# Led_Matrix_3.net
KiCad netlist of a schematic drawn in Altium Designer
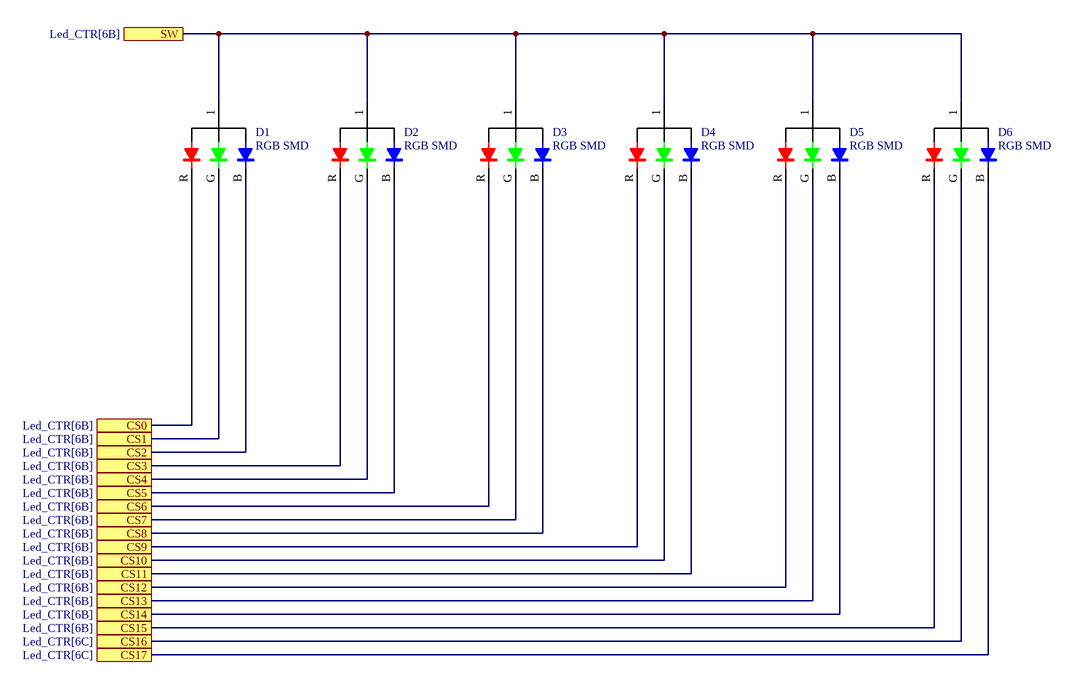
[diagram p0: Led_Matrix_3.SchDoc]

(export (version "E")
  (design (tool "Eeschema 10.0.6"))
  (components
    (comp (ref "D1")
      (value "RGB SMD")
      (footprint "LRTB_R48G")
      (description "LED Tri-Color Blue/Green/Red, 4-Pin Chip, 125 mcd, 2.7V, 10mA")
      (fields
        (field (name "MANUFACTURER") "Osram Opto")
        (field (name "MANUFACTURER PART NUMBER") "LRTB R48G")
      )
      (libsource (lib "Led_Matrix") (part "LED_RGB_SMD-4PIN_LRTB-R48G"))
    )
    (comp (ref "D2")
      (value "RGB SMD")
      (footprint "LRTB_R48G")
      (description "LED Tri-Color Blue/Green/Red, 4-Pin Chip, 125 mcd, 2.7V, 10mA")
      (fields
        (field (name "MANUFACTURER") "Osram Opto")
        (field (name "MANUFACTURER PART NUMBER") "LRTB R48G")
      )
      (libsource (lib "Led_Matrix") (part "LED_RGB_SMD-4PIN_LRTB-R48G"))
    )
    (comp (ref "D3")
      (value "RGB SMD")
      (footprint "LRTB_R48G")
      (description "LED Tri-Color Blue/Green/Red, 4-Pin Chip, 125 mcd, 2.7V, 10mA")
      (fields
        (field (name "MANUFACTURER") "Osram Opto")
        (field (name "MANUFACTURER PART NUMBER") "LRTB R48G")
      )
      (libsource (lib "Led_Matrix") (part "LED_RGB_SMD-4PIN_LRTB-R48G"))
    )
    (comp (ref "D4")
      (value "RGB SMD")
      (footprint "LRTB_R48G")
      (description "LED Tri-Color Blue/Green/Red, 4-Pin Chip, 125 mcd, 2.7V, 10mA")
      (fields
        (field (name "MANUFACTURER") "Osram Opto")
        (field (name "MANUFACTURER PART NUMBER") "LRTB R48G")
      )
      (libsource (lib "Led_Matrix") (part "LED_RGB_SMD-4PIN_LRTB-R48G"))
    )
    (comp (ref "D5")
      (value "RGB SMD")
      (footprint "LRTB_R48G")
      (description "LED Tri-Color Blue/Green/Red, 4-Pin Chip, 125 mcd, 2.7V, 10mA")
      (fields
        (field (name "MANUFACTURER") "Osram Opto")
        (field (name "MANUFACTURER PART NUMBER") "LRTB R48G")
      )
      (libsource (lib "Led_Matrix") (part "LED_RGB_SMD-4PIN_LRTB-R48G"))
    )
    (comp (ref "D6")
      (value "RGB SMD")
      (footprint "LRTB_R48G")
      (description "LED Tri-Color Blue/Green/Red, 4-Pin Chip, 125 mcd, 2.7V, 10mA")
      (fields
        (field (name "MANUFACTURER") "Osram Opto")
        (field (name "MANUFACTURER PART NUMBER") "LRTB R48G")
      )
      (libsource (lib "Led_Matrix") (part "LED_RGB_SMD-4PIN_LRTB-R48G"))
    )
  )
  (nets
    (net (code "1") (name "/CS0") (class "Default")
      (node (ref "D1") (pin "R") (pinfunction "R_R") (pintype "passive"))
    )
    (net (code "2") (name "/CS1") (class "Default")
      (node (ref "D1") (pin "G") (pinfunction "G_G") (pintype "passive"))
    )
    (net (code "3") (name "/CS2") (class "Default")
      (node (ref "D1") (pin "B") (pinfunction "B_B") (pintype "passive"))
    )
    (net (code "4") (name "/CS3") (class "Default")
      (node (ref "D2") (pin "R") (pinfunction "R_R") (pintype "passive"))
    )
    (net (code "5") (name "/CS4") (class "Default")
      (node (ref "D2") (pin "G") (pinfunction "G_G") (pintype "passive"))
    )
    (net (code "6") (name "/CS5") (class "Default")
      (node (ref "D2") (pin "B") (pinfunction "B_B") (pintype "passive"))
    )
    (net (code "7") (name "/CS6") (class "Default")
      (node (ref "D3") (pin "R") (pinfunction "R_R") (pintype "passive"))
    )
    (net (code "8") (name "/CS7") (class "Default")
      (node (ref "D3") (pin "G") (pinfunction "G_G") (pintype "passive"))
    )
    (net (code "9") (name "/CS8") (class "Default")
      (node (ref "D3") (pin "B") (pinfunction "B_B") (pintype "passive"))
    )
    (net (code "10") (name "/CS9") (class "Default")
      (node (ref "D4") (pin "R") (pinfunction "R_R") (pintype "passive"))
    )
    (net (code "11") (name "/CS10") (class "Default")
      (node (ref "D4") (pin "G") (pinfunction "G_G") (pintype "passive"))
    )
    (net (code "12") (name "/CS11") (class "Default")
      (node (ref "D4") (pin "B") (pinfunction "B_B") (pintype "passive"))
    )
    (net (code "13") (name "/CS12") (class "Default")
      (node (ref "D5") (pin "R") (pinfunction "R_R") (pintype "passive"))
    )
    (net (code "14") (name "/CS13") (class "Default")
      (node (ref "D5") (pin "G") (pinfunction "G_G") (pintype "passive"))
    )
    (net (code "15") (name "/CS14") (class "Default")
      (node (ref "D5") (pin "B") (pinfunction "B_B") (pintype "passive"))
    )
    (net (code "16") (name "/CS15") (class "Default")
      (node (ref "D6") (pin "R") (pinfunction "R_R") (pintype "passive"))
    )
    (net (code "17") (name "/CS16") (class "Default")
      (node (ref "D6") (pin "G") (pinfunction "G_G") (pintype "passive"))
    )
    (net (code "18") (name "/CS17") (class "Default")
      (node (ref "D6") (pin "B") (pinfunction "B_B") (pintype "passive"))
    )
    (net (code "19") (name "/SW") (class "Default")
      (node (ref "D1") (pin "1") (pinfunction "1_1") (pintype "passive"))
      (node (ref "D2") (pin "1") (pinfunction "1_1") (pintype "passive"))
      (node (ref "D3") (pin "1") (pinfunction "1_1") (pintype "passive"))
      (node (ref "D4") (pin "1") (pinfunction "1_1") (pintype "passive"))
      (node (ref "D5") (pin "1") (pinfunction "1_1") (pintype "passive"))
      (node (ref "D6") (pin "1") (pinfunction "1_1") (pintype "passive"))
    )
  )
)
